# SPI_Extender_2.net
KiCad netlist of a schematic drawn in Altium Designer
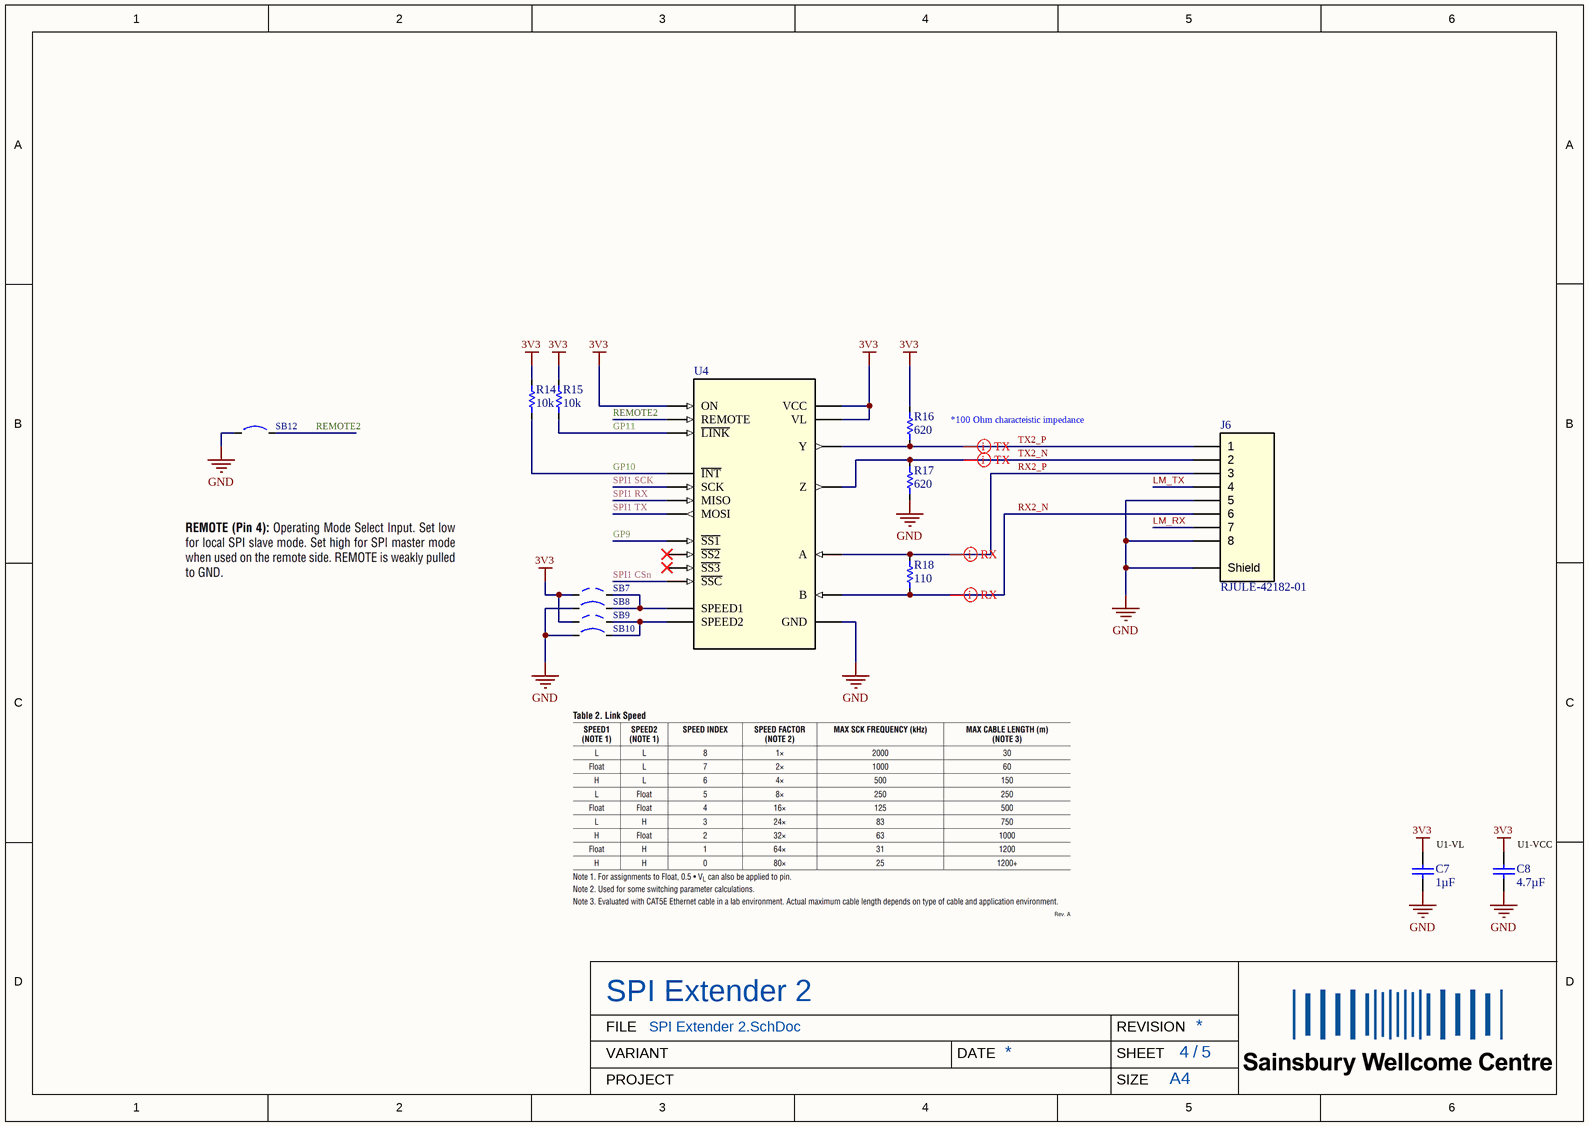
[diagram p0: SPI Extender 2.SchDoc]

(export (version "E")
  (design (tool "Eeschema 10.0.6"))
  (components
    (comp (ref "C7")
      (value "1µF")
      (footprint "FP-GRM188-0_1-e0_2_0_5-IPC_B")
      (description "1µF ±10% 25V Ceramic Capacitor X7R 0603 (1608 Metric)")
      (fields (field (name "VOLTAGE") "25V") (field (name "TOLERANCE") "10%"))
      (libsource (lib "Sainsbury Wellcome Centre") (part "Cap"))
    )
    (comp (ref "C8")
      (value "4.7µF")
      (footprint "CAPC2012X88N")
      (description "4.7uF ±5% 16V Ceramic Capacitor X7R 0805 (2012 Metric)")
      (fields (field (name "TOLERANCE") "5%") (field (name "VOLTAGE") "16V"))
      (libsource (lib "Sainsbury Wellcome Centre") (part "Cap"))
    )
    (comp (ref "J6")
      (value "RJULE4218201")
      (footprint "RJULE-42182-01 - RM")
      (description "Modular Jack - Right Angle, Input Output Connectors RJ45, 8P8C, Without LEDs, Shield.")
      (fields (field (name "PARTNUMBER") "RJULE-42182-01"))
      (libsource (lib "Sainsbury Wellcome Centre") (part "RJULE-42182-01"))
    )
    (comp (ref "R14")
      (value "10k")
      (footprint "FP-CPF0603-IPC_B")
      (description "Surface Mount Resistor 10k Ohm 1/16 W 0.1% 0603 (1608 Metric)")
      (fields (field (name "TOLERANCE") "0.1%") (field (name "Comment") "R0603-10k-1/16W-0.1%"))
      (libsource (lib "Sainsbury Wellcome Centre") (part "Res"))
    )
    (comp (ref "R15")
      (value "10k")
      (footprint "FP-CPF0603-IPC_B")
      (description "Surface Mount Resistor 10k Ohm 1/16 W 0.1% 0603 (1608 Metric)")
      (fields (field (name "TOLERANCE") "0.1%") (field (name "Comment") "R0603-10k-1/16W-0.1%"))
      (libsource (lib "Sainsbury Wellcome Centre") (part "Res"))
    )
    (comp (ref "R16")
      (value "620")
      (footprint "FP-CPF0603-IPC_B")
      (description "Surface Mount Resistor 620 Ohm 1/16 W 0.1% 0603 (1608 Metric)")
      (fields (field (name "TOLERANCE") "0.1%") (field (name "Comment") "R0603-620R-1/16W-0.1%"))
      (libsource (lib "Sainsbury Wellcome Centre") (part "Res"))
    )
    (comp (ref "R17")
      (value "620")
      (footprint "FP-CPF0603-IPC_B")
      (description "Surface Mount Resistor 620 Ohm 1/16 W 0.1% 0603 (1608 Metric)")
      (fields (field (name "TOLERANCE") "0.1%") (field (name "Comment") "R0603-620R-1/16W-0.1%"))
      (libsource (lib "Sainsbury Wellcome Centre") (part "Res"))
    )
    (comp (ref "R18")
      (value "110")
      (footprint "FP-CPF0603-IPC_B")
      (description "Surface Mount Resistor 110 Ohm 1/16 W 0.1% 0603 (1608 Metric)")
      (fields (field (name "TOLERANCE") "0.1%") (field (name "Comment") "R0603-110R-1/16W-0.1%"))
      (libsource (lib "Sainsbury Wellcome Centre") (part "Res"))
    )
    (comp (ref "SB7")
      (value "Solder Bridge 0603 Off")
      (footprint "Solder Bridge 0603 Off")
      (description "Solder Bridge 0603 OFF")
      (libsource (lib "Sainsbury Wellcome Centre") (part "Solder Bridge Off"))
    )
    (comp (ref "SB8")
      (value "Solder Bridge 0603 On")
      (footprint "Solder Bridge 0603 On")
      (description "Solder Bridge 0603 ON")
      (fields (field (name "PARTNUMBER") "R0603-0R-1/16W-0.1%"))
      (libsource (lib "Sainsbury Wellcome Centre") (part "Solder Bridge On"))
    )
    (comp (ref "SB9")
      (value "Solder Bridge 0603 Off")
      (footprint "Solder Bridge 0603 Off")
      (description "Solder Bridge 0603 OFF")
      (libsource (lib "Sainsbury Wellcome Centre") (part "Solder Bridge Off"))
    )
    (comp (ref "SB10")
      (value "Solder Bridge 0603 On")
      (footprint "Solder Bridge 0603 On")
      (description "Solder Bridge 0603 ON")
      (fields (field (name "PARTNUMBER") "R0603-0R-1/16W-0.1%"))
      (libsource (lib "Sainsbury Wellcome Centre") (part "Solder Bridge On"))
    )
    (comp (ref "SB12")
      (value "Solder Bridge 0603 On")
      (footprint "Solder Bridge 0603 On")
      (description "Solder Bridge 0603 ON")
      (fields (field (name "PARTNUMBER") "R0603-0R-1/16W-0.1%"))
      (libsource (lib "Sainsbury Wellcome Centre") (part "Solder Bridge On"))
    )
    (comp (ref "U4")
      (value "LTC4332HUFD#PBF")
      (footprint "FP-UFD-20-05-08-1711-IPC_B")
      (description "SPI Extender Over Rugged Differential Link")
      (libsource (lib "Sainsbury Wellcome Centre") (part "LTC4332"))
    )
  )
  (nets
    (net (code "1") (name "/GP9") (class "Default")
      (node (ref "U4") (pin "11") (pinfunction "~{SS1}_11") (pintype "input"))
    )
    (net (code "2") (name "/GP10") (class "Default")
      (node (ref "R14") (pin "1") (pinfunction "1_1") (pintype "passive"))
      (node (ref "U4") (pin "10") (pinfunction "~{INT}_10") (pintype "passive"))
    )
    (net (code "3") (name "/GP11") (class "Default")
      (node (ref "R15") (pin "1") (pinfunction "1_1") (pintype "passive"))
      (node (ref "U4") (pin "5") (pinfunction "~{LINK}_5") (pintype "input"))
    )
    (net (code "4") (name "/LM_RX") (class "Default")
      (node (ref "J6") (pin "7") (pinfunction "7_7") (pintype "passive"))
    )
    (net (code "5") (name "/LM_TX") (class "Default")
      (node (ref "J6") (pin "4") (pinfunction "4_4") (pintype "passive"))
    )
    (net (code "6") (name "/REMOTE2") (class "Default")
      (node (ref "SB12") (pin "2") (pinfunction "2_2") (pintype "passive"))
      (node (ref "U4") (pin "4") (pinfunction "REMOTE_4") (pintype "input"))
    )
    (net (code "7") (name "/RX2_N") (class "Default")
      (node (ref "J6") (pin "6") (pinfunction "6_6") (pintype "passive"))
      (node (ref "R18") (pin "1") (pinfunction "1_1") (pintype "passive"))
      (node (ref "U4") (pin "19") (pinfunction "B_19") (pintype "input"))
    )
    (net (code "8") (name "/RX2_P") (class "Default")
      (node (ref "J6") (pin "3") (pinfunction "3_3") (pintype "passive"))
      (node (ref "R18") (pin "2") (pinfunction "2_2") (pintype "passive"))
      (node (ref "U4") (pin "20") (pinfunction "A_20") (pintype "input"))
    )
    (net (code "9") (name "/SPI1 CSn") (class "Default")
      (node (ref "U4") (pin "6") (pinfunction "~{SSC}_6") (pintype "input"))
    )
    (net (code "10") (name "/SPI1 RX") (class "Default")
      (node (ref "U4") (pin "9") (pinfunction "MISO_9") (pintype "input"))
    )
    (net (code "11") (name "/SPI1 SCK") (class "Default")
      (node (ref "U4") (pin "7") (pinfunction "SCK_7") (pintype "input"))
    )
    (net (code "12") (name "/SPI1 TX") (class "Default")
      (node (ref "U4") (pin "8") (pinfunction "MOSI_8") (pintype "output"))
    )
    (net (code "13") (name "/TX2_N") (class "Default")
      (node (ref "J6") (pin "2") (pinfunction "2_2") (pintype "passive"))
      (node (ref "R17") (pin "2") (pinfunction "2_2") (pintype "passive"))
      (node (ref "U4") (pin "18") (pinfunction "Z_18") (pintype "output"))
    )
    (net (code "14") (name "/TX2_P") (class "Default")
      (node (ref "J6") (pin "1") (pinfunction "1_1") (pintype "passive"))
      (node (ref "R16") (pin "1") (pinfunction "1_1") (pintype "passive"))
      (node (ref "U4") (pin "17") (pinfunction "Y_17") (pintype "output"))
    )
    (net (code "15") (name "3V3") (class "Default")
      (node (ref "C7") (pin "2") (pinfunction "2_2") (pintype "passive"))
      (node (ref "C8") (pin "2") (pinfunction "2_2") (pintype "passive"))
      (node (ref "R14") (pin "2") (pinfunction "2_2") (pintype "passive"))
      (node (ref "R15") (pin "2") (pinfunction "2_2") (pintype "passive"))
      (node (ref "R16") (pin "2") (pinfunction "2_2") (pintype "passive"))
      (node (ref "SB7") (pin "1") (pinfunction "1_1") (pintype "passive"))
      (node (ref "SB9") (pin "1") (pinfunction "1_1") (pintype "passive"))
      (node (ref "U4") (pin "1") (pinfunction "VCC_1") (pintype "power_in"))
      (node (ref "U4") (pin "2") (pinfunction "VL_2") (pintype "power_in"))
      (node (ref "U4") (pin "3") (pinfunction "ON_3") (pintype "input"))
    )
    (net (code "16") (name "GND") (class "Default")
      (node (ref "C7") (pin "1") (pinfunction "1_1") (pintype "passive"))
      (node (ref "C8") (pin "1") (pinfunction "1_1") (pintype "passive"))
      (node (ref "J6") (pin "5") (pinfunction "5_5") (pintype "passive"))
      (node (ref "J6") (pin "8") (pinfunction "8_8") (pintype "passive"))
      (node (ref "J6") (pin "MH") (pinfunction "Shield_MH") (pintype "passive"))
      (node (ref "R17") (pin "1") (pinfunction "1_1") (pintype "passive"))
      (node (ref "SB10") (pin "1") (pinfunction "1_1") (pintype "passive"))
      (node (ref "SB12") (pin "1") (pinfunction "1_1") (pintype "passive"))
      (node (ref "SB8") (pin "1") (pinfunction "1_1") (pintype "passive"))
      (node (ref "U4") (pin "16") (pinfunction "GND_16") (pintype "power_in"))
    )
    (net (code "17") (name "Net-(U4-SPEED1)") (class "Default")
      (node (ref "SB7") (pin "2") (pinfunction "2_2") (pintype "passive"))
      (node (ref "SB8") (pin "2") (pinfunction "2_2") (pintype "passive"))
      (node (ref "U4") (pin "14") (pinfunction "SPEED1_14") (pintype "passive"))
    )
    (net (code "18") (name "Net-(U4-SPEED2)") (class "Default")
      (node (ref "SB10") (pin "2") (pinfunction "2_2") (pintype "passive"))
      (node (ref "SB9") (pin "2") (pinfunction "2_2") (pintype "passive"))
      (node (ref "U4") (pin "15") (pinfunction "SPEED2_15") (pintype "passive"))
    )
    (net (code "19") (name "unconnected-(U4-~{SS2}-Pad12)") (class "Default")
      (node (ref "U4") (pin "12") (pinfunction "~{SS2}_12") (pintype "input+no_connect"))
    )
    (net (code "20") (name "unconnected-(U4-~{SS3}-Pad13)") (class "Default")
      (node (ref "U4") (pin "13") (pinfunction "~{SS3}_13") (pintype "input+no_connect"))
    )
  )
)
